# tongxun.net
KiCad netlist of a schematic drawn in Altium Designer
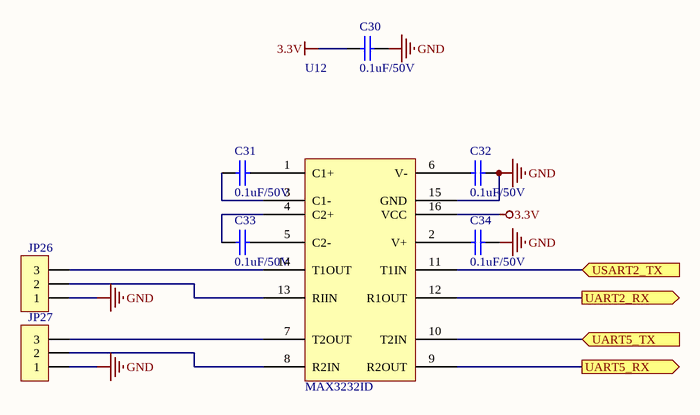
[diagram p0: tongxun.SchDoc]

(export (version "E")
  (design (tool "Eeschema 10.0.6"))
  (components
    (comp (ref "C30")
      (value "0.1uF/50V")
      (footprint "C 0603_L")
      (description "片式X7R电容")
      (libsource (lib "*") (part "CAP"))
    )
    (comp (ref "C31")
      (value "0.1uF/50V")
      (footprint "C 0603_L")
      (description "片式X7R电容")
      (libsource (lib "*") (part "CAP"))
    )
    (comp (ref "C32")
      (value "0.1uF/50V")
      (footprint "C 0603_L")
      (description "片式X7R电容")
      (libsource (lib "*") (part "CAP"))
    )
    (comp (ref "C33")
      (value "0.1uF/50V")
      (footprint "C 0603_L")
      (description "片式X7R电容")
      (libsource (lib "*") (part "CAP"))
    )
    (comp (ref "C34")
      (value "0.1uF/50V")
      (footprint "C 0603_L")
      (description "片式X7R电容")
      (libsource (lib "*") (part "CAP"))
    )
    (comp (ref "JP26")
      (value "HDR-1X3")
      (footprint "XH2.54-LI-3P")
      (description "3P接插件")
      (fields (field (name "版权归属") "源创客"))
      (libsource (lib "4.5   - 接插件-脚距2.54") (part "Header 3"))
    )
    (comp (ref "JP27")
      (value "HDR-1X3")
      (footprint "XH2.54-LI-3P")
      (description "3P接插件")
      (fields (field (name "版权归属") "源创客"))
      (libsource (lib "4.5   - 接插件-脚距2.54") (part "Header 3"))
    )
    (comp (ref "U12")
      (value "MAX3232ID")
      (footprint "SOP16_n")
      (description "贴片集成电路")
      (libsource (lib "*") (part "MAX232"))
    )
  )
  (nets
    (net (code "1") (name "/UART2_RX") (class "Default")
      (node (ref "U12") (pin "12") (pinfunction "R1OUT_12") (pintype "passive"))
    )
    (net (code "2") (name "/UART5_RX") (class "Default")
      (node (ref "U12") (pin "9") (pinfunction "R2OUT_9") (pintype "passive"))
    )
    (net (code "3") (name "/UART5_TX") (class "Default")
      (node (ref "U12") (pin "10") (pinfunction "T2IN_10") (pintype "passive"))
    )
    (net (code "4") (name "/USART2_TX") (class "Default")
      (node (ref "U12") (pin "11") (pinfunction "T1IN_11") (pintype "passive"))
    )
    (net (code "5") (name "3.3V") (class "Default")
      (node (ref "C30") (pin "1") (pinfunction "1_1") (pintype "passive"))
      (node (ref "U12") (pin "16") (pinfunction "VCC_16") (pintype "passive"))
    )
    (net (code "6") (name "GND") (class "Default")
      (node (ref "C30") (pin "2") (pinfunction "2_2") (pintype "passive"))
      (node (ref "C32") (pin "2") (pinfunction "2_2") (pintype "passive"))
      (node (ref "C34") (pin "2") (pinfunction "2_2") (pintype "passive"))
      (node (ref "JP26") (pin "1") (pinfunction "1_1") (pintype "passive"))
      (node (ref "JP27") (pin "1") (pinfunction "1_1") (pintype "passive"))
      (node (ref "U12") (pin "15") (pinfunction "GND_15") (pintype "passive"))
    )
    (net (code "7") (name "Net-(U12-C1+)") (class "Default")
      (node (ref "C31") (pin "2") (pinfunction "2_2") (pintype "passive"))
      (node (ref "U12") (pin "1") (pinfunction "C1+_1") (pintype "passive"))
    )
    (net (code "8") (name "Net-(U12-C1-)") (class "Default")
      (node (ref "C31") (pin "1") (pinfunction "1_1") (pintype "passive"))
      (node (ref "U12") (pin "3") (pinfunction "C1-_3") (pintype "passive"))
    )
    (net (code "9") (name "Net-(U12-C2+)") (class "Default")
      (node (ref "C33") (pin "1") (pinfunction "1_1") (pintype "passive"))
      (node (ref "U12") (pin "4") (pinfunction "C2+_4") (pintype "passive"))
    )
    (net (code "10") (name "Net-(U12-C2-)") (class "Default")
      (node (ref "C33") (pin "2") (pinfunction "2_2") (pintype "passive"))
      (node (ref "U12") (pin "5") (pinfunction "C2-_5") (pintype "passive"))
    )
    (net (code "11") (name "Net-(U12-R2IN)") (class "Default")
      (node (ref "JP27") (pin "2") (pinfunction "2_2") (pintype "passive"))
      (node (ref "U12") (pin "8") (pinfunction "R2IN_8") (pintype "passive"))
    )
    (net (code "12") (name "Net-(U12-RIIN)") (class "Default")
      (node (ref "JP26") (pin "2") (pinfunction "2_2") (pintype "passive"))
      (node (ref "U12") (pin "13") (pinfunction "RIIN_13") (pintype "passive"))
    )
    (net (code "13") (name "Net-(U12-T1OUT)") (class "Default")
      (node (ref "JP26") (pin "3") (pinfunction "3_3") (pintype "passive"))
      (node (ref "U12") (pin "14") (pinfunction "T1OUT_14") (pintype "passive"))
    )
    (net (code "14") (name "Net-(U12-T2OUT)") (class "Default")
      (node (ref "JP27") (pin "3") (pinfunction "3_3") (pintype "passive"))
      (node (ref "U12") (pin "7") (pinfunction "T2OUT_7") (pintype "passive"))
    )
    (net (code "15") (name "Net-(U12-V+)") (class "Default")
      (node (ref "C34") (pin "1") (pinfunction "1_1") (pintype "passive"))
      (node (ref "U12") (pin "2") (pinfunction "V+_2") (pintype "passive"))
    )
    (net (code "16") (name "Net-(U12-V-)") (class "Default")
      (node (ref "C32") (pin "1") (pinfunction "1_1") (pintype "passive"))
      (node (ref "U12") (pin "6") (pinfunction "V-_6") (pintype "passive"))
    )
  )
)
